# reefingBrd.net
KiCad netlist of a schematic drawn in EAGLE
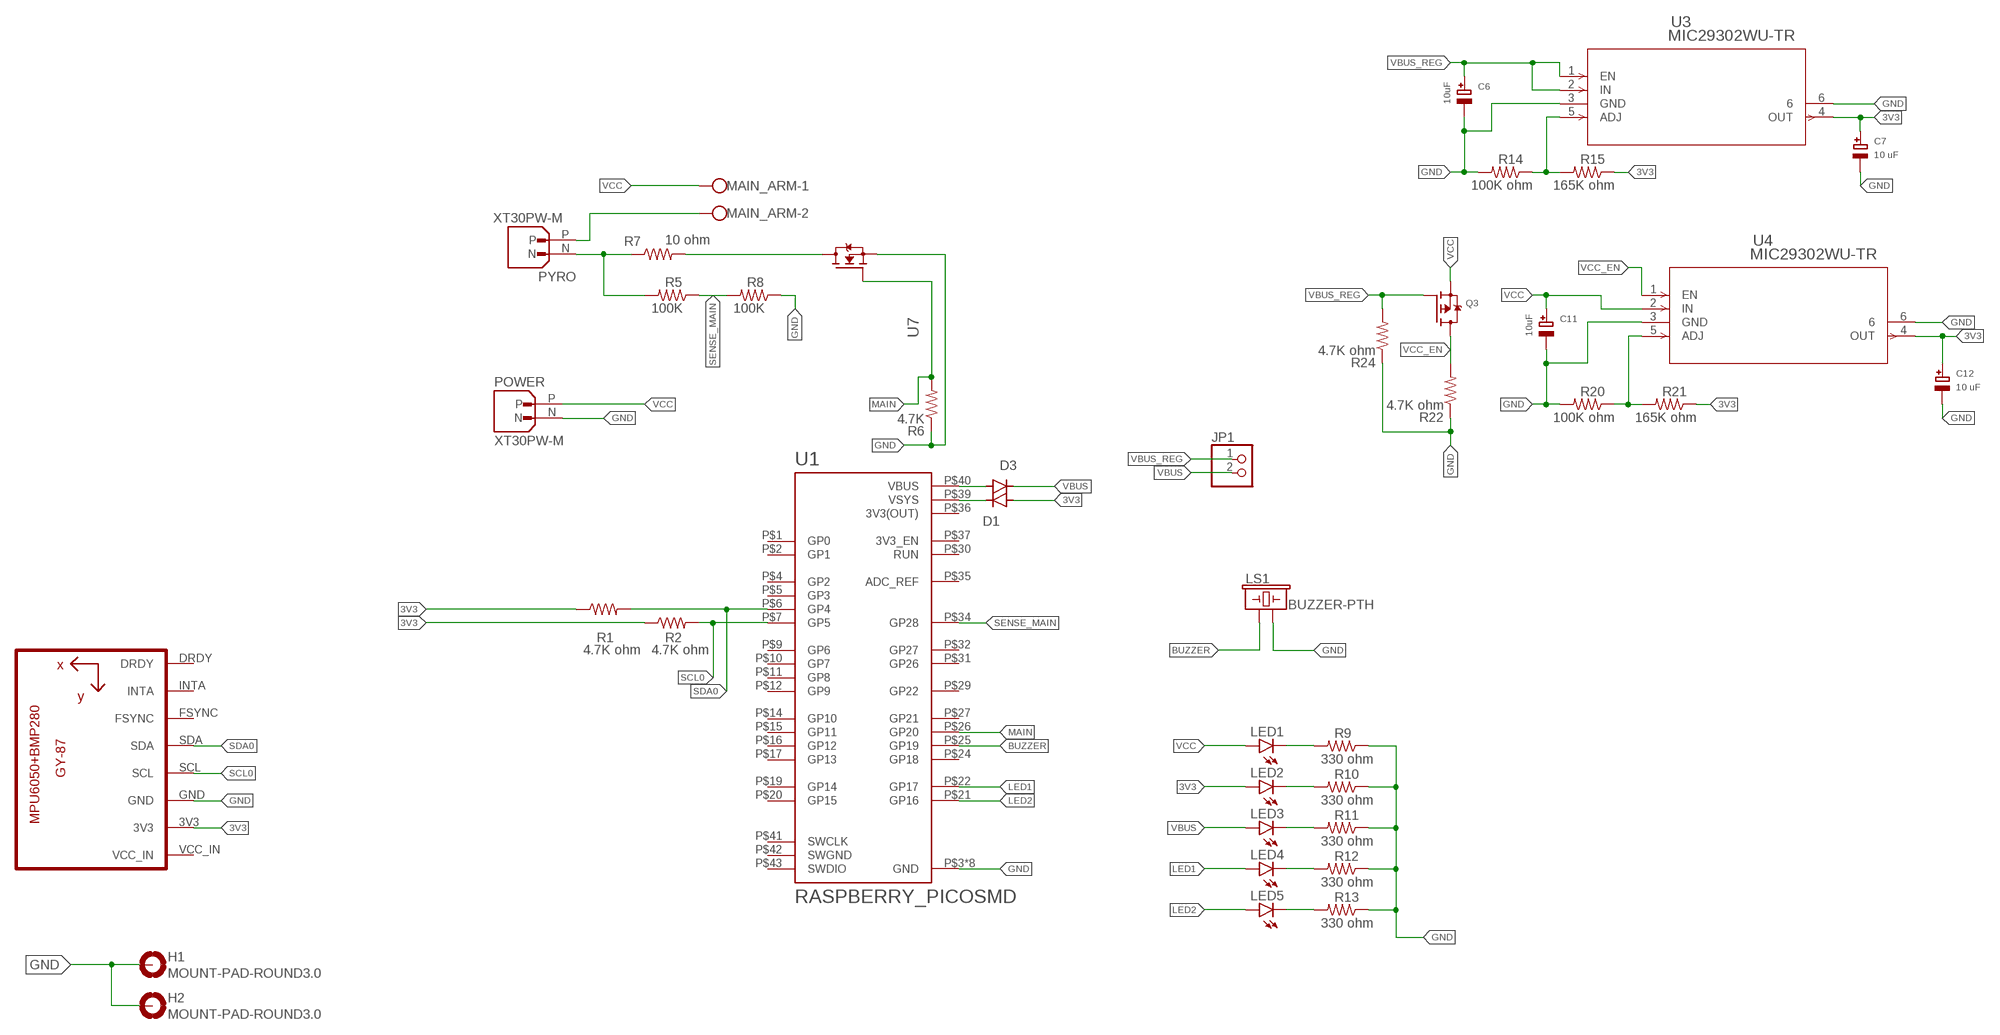
[diagram p0: schematic, sheet 1]

(export (version "E")
  (design (tool "Eeschema 10.0.6"))
  (components
    (comp (ref "C6")
      (value "10uF")
      (footprint "eagle-import:EIA3216-18_A-W")
      (libsource (lib "eagle-import") (part "CAP_TANTALUMA/3216_WAVE"))
    )
    (comp (ref "C7")
      (value "10 uF")
      (footprint "eagle-import:EIA3216-18_A-W")
      (libsource (lib "eagle-import") (part "CAP_TANTALUMA/3216_WAVE"))
    )
    (comp (ref "C11")
      (value "10uF")
      (footprint "eagle-import:EIA3216-18_A-W")
      (libsource (lib "eagle-import") (part "CAP_TANTALUMA/3216_WAVE"))
    )
    (comp (ref "C12")
      (value "10 uF")
      (footprint "eagle-import:EIA3216-18_A-W")
      (libsource (lib "eagle-import") (part "CAP_TANTALUMA/3216_WAVE"))
    )
    (comp (ref "D1")
      (value "1N4004")
      (footprint "eagle-import:DO41-10")
      (libsource (lib "eagle-import") (part "1N4004"))
    )
    (comp (ref "D3")
      (value "1N4004")
      (footprint "eagle-import:DO41-10")
      (libsource (lib "eagle-import") (part "1N4004"))
    )
    (comp (ref "H1")
      (value "MOUNT-PAD-ROUND3.0")
      (footprint "eagle-import:3,0-PAD")
      (libsource (lib "eagle-import") (part "MOUNT-PAD-ROUND3.0"))
    )
    (comp (ref "H2")
      (value "MOUNT-PAD-ROUND3.0")
      (footprint "eagle-import:3,0-PAD")
      (libsource (lib "eagle-import") (part "MOUNT-PAD-ROUND3.0"))
    )
    (comp (ref "JP1")
      (value "PINHD-1X2")
      (footprint "eagle-import:1X02")
      (libsource (lib "eagle-import") (part "PINHD-1X2"))
    )
    (comp (ref "LED1")
      (value "LEDCHIPLED_1206")
      (footprint "eagle-import:CHIPLED_1206")
      (libsource (lib "eagle-import") (part "LEDCHIPLED_1206"))
    )
    (comp (ref "LED2")
      (value "LEDCHIPLED_1206")
      (footprint "eagle-import:CHIPLED_1206")
      (libsource (lib "eagle-import") (part "LEDCHIPLED_1206"))
    )
    (comp (ref "LED3")
      (value "LEDCHIPLED_1206")
      (footprint "eagle-import:CHIPLED_1206")
      (libsource (lib "eagle-import") (part "LEDCHIPLED_1206"))
    )
    (comp (ref "LED4")
      (value "LEDCHIPLED_1206")
      (footprint "eagle-import:CHIPLED_1206")
      (libsource (lib "eagle-import") (part "LEDCHIPLED_1206"))
    )
    (comp (ref "LED5")
      (value "LEDCHIPLED_1206")
      (footprint "eagle-import:CHIPLED_1206")
      (libsource (lib "eagle-import") (part "LEDCHIPLED_1206"))
    )
    (comp (ref "LS1")
      (value "BUZZER-PTH")
      (footprint "eagle-import:BUZZER-12MM")
      (libsource (lib "eagle-import") (part "BUZZER-PTH"))
    )
    (comp (ref "MAIN_ARM")
      (value "W237-102")
      (footprint "eagle-import:W237-102")
      (fields (field (name "MPN") "237-102"))
      (libsource (lib "eagle-import") (part "W237-102"))
    )
    (comp (ref "POWER")
      (value "XT30PW-M")
      (footprint "eagle-import:AMASS_XT30PW-M")
      (fields (field (name "MF") "AMASS"))
      (libsource (lib "eagle-import") (part "XT30PW-M"))
    )
    (comp (ref "PYRO")
      (value "XT30PW-M")
      (footprint "eagle-import:AMASS_XT30PW-M")
      (fields (field (name "MF") "AMASS"))
      (libsource (lib "eagle-import") (part "XT30PW-M"))
    )
    (comp (ref "Q3")
      (value "MOSFET-PWIDE")
      (footprint "eagle-import:SOT23-WIDE")
      (libsource (lib "eagle-import") (part "MOSFET-PWIDE"))
    )
    (comp (ref "R1")
      (value "4.7K ohm")
      (footprint "eagle-import:R0805")
      (libsource (lib "eagle-import") (part "R-US_R0805"))
    )
    (comp (ref "R2")
      (value "4.7K ohm")
      (footprint "eagle-import:R0805")
      (libsource (lib "eagle-import") (part "R-US_R0805"))
    )
    (comp (ref "R5")
      (value "100K")
      (footprint "eagle-import:R0805")
      (libsource (lib "eagle-import") (part "R-US_R0805"))
    )
    (comp (ref "R6")
      (value "4.7K")
      (footprint "eagle-import:R0805")
      (libsource (lib "eagle-import") (part "R-US_R0805"))
    )
    (comp (ref "R7")
      (value "10 ohm")
      (footprint "eagle-import:0207_10")
      (libsource (lib "eagle-import") (part "R-US_0207/10"))
    )
    (comp (ref "R8")
      (value "100K")
      (footprint "eagle-import:R0805")
      (libsource (lib "eagle-import") (part "R-US_R0805"))
    )
    (comp (ref "R9")
      (value "330 ohm")
      (footprint "eagle-import:R0805")
      (libsource (lib "eagle-import") (part "R-US_R0805"))
    )
    (comp (ref "R10")
      (value "330 ohm")
      (footprint "eagle-import:R0805")
      (libsource (lib "eagle-import") (part "R-US_R0805"))
    )
    (comp (ref "R11")
      (value "330 ohm")
      (footprint "eagle-import:R0805")
      (libsource (lib "eagle-import") (part "R-US_R0805"))
    )
    (comp (ref "R12")
      (value "330 ohm")
      (footprint "eagle-import:R0805")
      (libsource (lib "eagle-import") (part "R-US_R0805"))
    )
    (comp (ref "R13")
      (value "330 ohm")
      (footprint "eagle-import:R0805")
      (libsource (lib "eagle-import") (part "R-US_R0805"))
    )
    (comp (ref "R14")
      (value "100K ohm")
      (footprint "eagle-import:R0805")
      (libsource (lib "eagle-import") (part "R-US_R0805"))
    )
    (comp (ref "R15")
      (value "165K ohm")
      (footprint "eagle-import:R0805")
      (libsource (lib "eagle-import") (part "R-US_R0805"))
    )
    (comp (ref "R20")
      (value "100K ohm")
      (footprint "eagle-import:R0805")
      (libsource (lib "eagle-import") (part "R-US_R0805"))
    )
    (comp (ref "R21")
      (value "165K ohm")
      (footprint "eagle-import:R0805")
      (libsource (lib "eagle-import") (part "R-US_R0805"))
    )
    (comp (ref "R22")
      (value "4.7K ohm")
      (footprint "eagle-import:R0805")
      (libsource (lib "eagle-import") (part "R-US_R0805"))
    )
    (comp (ref "R24")
      (value "4.7K ohm")
      (footprint "eagle-import:R0805")
      (libsource (lib "eagle-import") (part "R-US_R0805"))
    )
    (comp (ref "U1")
      (value "RASPBERRY_PICOSMD")
      (footprint "eagle-import:PICO-PKG-SMD")
      (libsource (lib "eagle-import") (part "RASPBERRY_PICOSMD"))
    )
    (comp (ref "U2")
      (value "GY-521MPU6050")
      (footprint "eagle-import:GY-521")
      (libsource (lib "eagle-import") (part "GY-521MPU6050"))
    )
    (comp (ref "U3")
      (value "MIC29302WU-TR")
      (footprint "eagle-import:TO-263-5_MCH")
      (fields (field (name "COPYRIGHT") "Copyright (C) 2024 Ultra Librarian. All rights reserved."))
      (libsource (lib "eagle-import") (part "MIC29302WU-TR"))
    )
    (comp (ref "U4")
      (value "MIC29302WU-TR")
      (footprint "eagle-import:TO-263-5_MCH")
      (fields (field (name "COPYRIGHT") "Copyright (C) 2024 Ultra Librarian. All rights reserved."))
      (libsource (lib "eagle-import") (part "MIC29302WU-TR"))
    )
    (comp (ref "U7")
      (value "IRF540NPBF")
      (footprint "eagle-import:TO254P1054X469X1930-3")
      (fields (field (name "MF") "Infineon"))
      (libsource (lib "eagle-import") (part "IRF540NPBF"))
    )
  )
  (nets
    (net (code "1") (name "/3V3(OUT)") (class "Default")
      (node (ref "U1") (pin "P$36") (pinfunction "3V3(OUT)_P$36") (pintype "power_in"))
    )
    (net (code "2") (name "/SWGND") (class "Default")
      (node (ref "U1") (pin "P$42") (pinfunction "SWGND_P$42") (pintype "power_in"))
    )
    (net (code "3") (name "3V3") (class "Default")
      (node (ref "C12") (pin "+") (pinfunction "+_+") (pintype "passive"))
      (node (ref "C7") (pin "+") (pinfunction "+_+") (pintype "passive"))
      (node (ref "D1") (pin "A") (pinfunction "A_A") (pintype "passive"))
      (node (ref "LED2") (pin "A") (pinfunction "A_A") (pintype "passive"))
      (node (ref "R1") (pin "1") (pinfunction "1_1") (pintype "passive"))
      (node (ref "R15") (pin "1") (pinfunction "1_1") (pintype "passive"))
      (node (ref "R2") (pin "1") (pinfunction "1_1") (pintype "passive"))
      (node (ref "R21") (pin "1") (pinfunction "1_1") (pintype "passive"))
      (node (ref "U2") (pin "3V3") (pinfunction "3V3_3V3") (pintype "bidirectional"))
      (node (ref "U3") (pin "4") (pinfunction "OUT_4") (pintype "output"))
      (node (ref "U4") (pin "4") (pinfunction "OUT_4") (pintype "output"))
    )
    (net (code "4") (name "BUZZER") (class "Default")
      (node (ref "LS1") (pin "+") (pinfunction "1_+") (pintype "passive"))
      (node (ref "U1") (pin "P$25") (pinfunction "GP19_P$25") (pintype "bidirectional"))
    )
    (net (code "5") (name "GND") (class "Default")
      (node (ref "C11") (pin "-") (pinfunction "-_-") (pintype "passive"))
      (node (ref "C12") (pin "-") (pinfunction "-_-") (pintype "passive"))
      (node (ref "C6") (pin "-") (pinfunction "-_-") (pintype "passive"))
      (node (ref "C7") (pin "-") (pinfunction "-_-") (pintype "passive"))
      (node (ref "H1") (pin "B3,0") (pinfunction "MOUNT_B3,0") (pintype "passive"))
      (node (ref "H2") (pin "B3,0") (pinfunction "MOUNT_B3,0") (pintype "passive"))
      (node (ref "LS1") (pin "-") (pinfunction "2_-") (pintype "passive"))
      (node (ref "POWER") (pin "N") (pinfunction "N_N") (pintype "power_in"))
      (node (ref "R10") (pin "1") (pinfunction "1_1") (pintype "passive"))
      (node (ref "R11") (pin "1") (pinfunction "1_1") (pintype "passive"))
      (node (ref "R12") (pin "1") (pinfunction "1_1") (pintype "passive"))
      (node (ref "R13") (pin "1") (pinfunction "1_1") (pintype "passive"))
      (node (ref "R14") (pin "2") (pinfunction "2_2") (pintype "passive"))
      (node (ref "R20") (pin "2") (pinfunction "2_2") (pintype "passive"))
      (node (ref "R22") (pin "1") (pinfunction "1_1") (pintype "passive"))
      (node (ref "R24") (pin "1") (pinfunction "1_1") (pintype "passive"))
      (node (ref "R6") (pin "1") (pinfunction "1_1") (pintype "passive"))
      (node (ref "R8") (pin "1") (pinfunction "1_1") (pintype "passive"))
      (node (ref "R9") (pin "1") (pinfunction "1_1") (pintype "passive"))
      (node (ref "U1") (pin "P$13") (pinfunction "GND_P$13") (pintype "power_in"))
      (node (ref "U1") (pin "P$18") (pinfunction "GND_P$18") (pintype "power_in"))
      (node (ref "U1") (pin "P$23") (pinfunction "GND_P$23") (pintype "power_in"))
      (node (ref "U1") (pin "P$28") (pinfunction "GND_P$28") (pintype "power_in"))
      (node (ref "U1") (pin "P$3") (pinfunction "GND_P$3") (pintype "power_in"))
      (node (ref "U1") (pin "P$33") (pinfunction "GND_P$33") (pintype "power_in"))
      (node (ref "U1") (pin "P$38") (pinfunction "GND_P$38") (pintype "power_in"))
      (node (ref "U1") (pin "P$8") (pinfunction "GND_P$8") (pintype "power_in"))
      (node (ref "U2") (pin "GND") (pinfunction "GND_GND") (pintype "bidirectional"))
      (node (ref "U3") (pin "3") (pinfunction "GND_3") (pintype "power_in"))
      (node (ref "U3") (pin "6") (pinfunction "6_6") (pintype "passive"))
      (node (ref "U4") (pin "3") (pinfunction "GND_3") (pintype "power_in"))
      (node (ref "U4") (pin "6") (pinfunction "6_6") (pintype "passive"))
      (node (ref "U7") (pin "3") (pinfunction "S_3") (pintype "passive"))
    )
    (net (code "6") (name "LED1") (class "Default")
      (node (ref "LED4") (pin "A") (pinfunction "A_A") (pintype "passive"))
      (node (ref "U1") (pin "P$22") (pinfunction "GP17_P$22") (pintype "bidirectional"))
    )
    (net (code "7") (name "LED2") (class "Default")
      (node (ref "LED5") (pin "A") (pinfunction "A_A") (pintype "passive"))
      (node (ref "U1") (pin "P$21") (pinfunction "GP16_P$21") (pintype "bidirectional"))
    )
    (net (code "8") (name "MAIN") (class "Default")
      (node (ref "R6") (pin "2") (pinfunction "2_2") (pintype "passive"))
      (node (ref "U1") (pin "P$26") (pinfunction "GP20_P$26") (pintype "bidirectional"))
      (node (ref "U7") (pin "1") (pinfunction "G_1") (pintype "passive"))
    )
    (net (code "9") (name "Net-(LED1-PadC)") (class "Default")
      (node (ref "LED1") (pin "C") (pinfunction "C_C") (pintype "passive"))
      (node (ref "R9") (pin "2") (pinfunction "2_2") (pintype "passive"))
    )
    (net (code "10") (name "Net-(LED2-PadC)") (class "Default")
      (node (ref "LED2") (pin "C") (pinfunction "C_C") (pintype "passive"))
      (node (ref "R10") (pin "2") (pinfunction "2_2") (pintype "passive"))
    )
    (net (code "11") (name "Net-(LED3-PadC)") (class "Default")
      (node (ref "LED3") (pin "C") (pinfunction "C_C") (pintype "passive"))
      (node (ref "R11") (pin "2") (pinfunction "2_2") (pintype "passive"))
    )
    (net (code "12") (name "Net-(LED4-PadC)") (class "Default")
      (node (ref "LED4") (pin "C") (pinfunction "C_C") (pintype "passive"))
      (node (ref "R12") (pin "2") (pinfunction "2_2") (pintype "passive"))
    )
    (net (code "13") (name "Net-(LED5-PadC)") (class "Default")
      (node (ref "LED5") (pin "C") (pinfunction "C_C") (pintype "passive"))
      (node (ref "R13") (pin "2") (pinfunction "2_2") (pintype "passive"))
    )
    (net (code "14") (name "Net-(MAIN_ARMB-KL)") (class "Default")
      (node (ref "MAIN_ARM") (pin "2") (pinfunction "KL_2") (pintype "passive"))
      (node (ref "PYRO") (pin "P") (pinfunction "P_P") (pintype "power_in"))
    )
    (net (code "15") (name "Net-(PYRO-PadN)") (class "Default")
      (node (ref "PYRO") (pin "N") (pinfunction "N_N") (pintype "power_in"))
      (node (ref "R5") (pin "2") (pinfunction "2_2") (pintype "passive"))
      (node (ref "R7") (pin "1") (pinfunction "1_1") (pintype "passive"))
    )
    (net (code "16") (name "Net-(U1-VBUS)") (class "Default")
      (node (ref "D3") (pin "A") (pinfunction "A_A") (pintype "passive"))
      (node (ref "U1") (pin "P$40") (pinfunction "VBUS_P$40") (pintype "power_in"))
    )
    (net (code "17") (name "Net-(U1-VSYS)") (class "Default")
      (node (ref "D1") (pin "C") (pinfunction "C_C") (pintype "passive"))
      (node (ref "U1") (pin "P$39") (pinfunction "VSYS_P$39") (pintype "power_in"))
    )
    (net (code "18") (name "Net-(U3-ADJ)") (class "Default")
      (node (ref "R14") (pin "1") (pinfunction "1_1") (pintype "passive"))
      (node (ref "R15") (pin "2") (pinfunction "2_2") (pintype "passive"))
      (node (ref "U3") (pin "5") (pinfunction "ADJ_5") (pintype "input"))
    )
    (net (code "19") (name "Net-(U4-ADJ)") (class "Default")
      (node (ref "R20") (pin "1") (pinfunction "1_1") (pintype "passive"))
      (node (ref "R21") (pin "2") (pinfunction "2_2") (pintype "passive"))
      (node (ref "U4") (pin "5") (pinfunction "ADJ_5") (pintype "input"))
    )
    (net (code "20") (name "Net-(U7-D)") (class "Default")
      (node (ref "R7") (pin "2") (pinfunction "2_2") (pintype "passive"))
      (node (ref "U7") (pin "2") (pinfunction "D_2") (pintype "passive"))
    )
    (net (code "21") (name "SCL0") (class "Default")
      (node (ref "R2") (pin "2") (pinfunction "2_2") (pintype "passive"))
      (node (ref "U1") (pin "P$7") (pinfunction "GP5_P$7") (pintype "bidirectional"))
      (node (ref "U2") (pin "SCL") (pinfunction "SCL_SCL") (pintype "bidirectional"))
    )
    (net (code "22") (name "SDA0") (class "Default")
      (node (ref "R1") (pin "2") (pinfunction "2_2") (pintype "passive"))
      (node (ref "U1") (pin "P$6") (pinfunction "GP4_P$6") (pintype "bidirectional"))
      (node (ref "U2") (pin "SDA") (pinfunction "SDA_SDA") (pintype "bidirectional"))
    )
    (net (code "23") (name "SENSE_MAIN") (class "Default")
      (node (ref "R5") (pin "1") (pinfunction "1_1") (pintype "passive"))
      (node (ref "R8") (pin "2") (pinfunction "2_2") (pintype "passive"))
      (node (ref "U1") (pin "P$34") (pinfunction "GP28_P$34") (pintype "bidirectional"))
    )
    (net (code "24") (name "VBUS") (class "Default")
      (node (ref "D3") (pin "C") (pinfunction "C_C") (pintype "passive"))
      (node (ref "JP1") (pin "2") (pinfunction "2_2") (pintype "passive"))
      (node (ref "LED3") (pin "A") (pinfunction "A_A") (pintype "passive"))
    )
    (net (code "25") (name "VBUS_REG") (class "Default")
      (node (ref "C6") (pin "+") (pinfunction "+_+") (pintype "passive"))
      (node (ref "JP1") (pin "1") (pinfunction "1_1") (pintype "passive"))
      (node (ref "Q3") (pin "1") (pinfunction "G_1") (pintype "passive"))
      (node (ref "R24") (pin "2") (pinfunction "2_2") (pintype "passive"))
      (node (ref "U3") (pin "1") (pinfunction "EN_1") (pintype "input"))
      (node (ref "U3") (pin "2") (pinfunction "IN_2") (pintype "input"))
    )
    (net (code "26") (name "VCC") (class "Default")
      (node (ref "C11") (pin "+") (pinfunction "+_+") (pintype "passive"))
      (node (ref "LED1") (pin "A") (pinfunction "A_A") (pintype "passive"))
      (node (ref "MAIN_ARM") (pin "1") (pinfunction "KL_1") (pintype "passive"))
      (node (ref "POWER") (pin "P") (pinfunction "P_P") (pintype "power_in"))
      (node (ref "Q3") (pin "2") (pinfunction "S_2") (pintype "passive"))
      (node (ref "U4") (pin "2") (pinfunction "IN_2") (pintype "input"))
    )
    (net (code "27") (name "VCC_EN") (class "Default")
      (node (ref "Q3") (pin "3") (pinfunction "D_3") (pintype "passive"))
      (node (ref "R22") (pin "2") (pinfunction "2_2") (pintype "passive"))
      (node (ref "U4") (pin "1") (pinfunction "EN_1") (pintype "input"))
    )
    (net (code "28") (name "unconnected-(U1-3V3_EN-PadP$37)") (class "Default")
      (node (ref "U1") (pin "P$37") (pinfunction "3V3_EN_P$37") (pintype "input"))
    )
    (net (code "29") (name "unconnected-(U1-ADC_REF-PadP$35)") (class "Default")
      (node (ref "U1") (pin "P$35") (pinfunction "ADC_REF_P$35") (pintype "input"))
    )
    (net (code "30") (name "unconnected-(U1-GP0-PadP$1)") (class "Default")
      (node (ref "U1") (pin "P$1") (pinfunction "GP0_P$1") (pintype "bidirectional"))
    )
    (net (code "31") (name "unconnected-(U1-GP1-PadP$2)") (class "Default")
      (node (ref "U1") (pin "P$2") (pinfunction "GP1_P$2") (pintype "bidirectional"))
    )
    (net (code "32") (name "unconnected-(U1-GP2-PadP$4)") (class "Default")
      (node (ref "U1") (pin "P$4") (pinfunction "GP2_P$4") (pintype "bidirectional"))
    )
    (net (code "33") (name "unconnected-(U1-GP3-PadP$5)") (class "Default")
      (node (ref "U1") (pin "P$5") (pinfunction "GP3_P$5") (pintype "bidirectional"))
    )
    (net (code "34") (name "unconnected-(U1-GP6-PadP$9)") (class "Default")
      (node (ref "U1") (pin "P$9") (pinfunction "GP6_P$9") (pintype "bidirectional"))
    )
    (net (code "35") (name "unconnected-(U1-GP7-PadP$10)") (class "Default")
      (node (ref "U1") (pin "P$10") (pinfunction "GP7_P$10") (pintype "bidirectional"))
    )
    (net (code "36") (name "unconnected-(U1-GP8-PadP$11)") (class "Default")
      (node (ref "U1") (pin "P$11") (pinfunction "GP8_P$11") (pintype "bidirectional"))
    )
    (net (code "37") (name "unconnected-(U1-GP9-PadP$12)") (class "Default")
      (node (ref "U1") (pin "P$12") (pinfunction "GP9_P$12") (pintype "bidirectional"))
    )
    (net (code "38") (name "unconnected-(U1-GP10-PadP$14)") (class "Default")
      (node (ref "U1") (pin "P$14") (pinfunction "GP10_P$14") (pintype "bidirectional"))
    )
    (net (code "39") (name "unconnected-(U1-GP11-PadP$15)") (class "Default")
      (node (ref "U1") (pin "P$15") (pinfunction "GP11_P$15") (pintype "bidirectional"))
    )
    (net (code "40") (name "unconnected-(U1-GP12-PadP$16)") (class "Default")
      (node (ref "U1") (pin "P$16") (pinfunction "GP12_P$16") (pintype "bidirectional"))
    )
    (net (code "41") (name "unconnected-(U1-GP13-PadP$17)") (class "Default")
      (node (ref "U1") (pin "P$17") (pinfunction "GP13_P$17") (pintype "bidirectional"))
    )
    (net (code "42") (name "unconnected-(U1-GP14-PadP$19)") (class "Default")
      (node (ref "U1") (pin "P$19") (pinfunction "GP14_P$19") (pintype "bidirectional"))
    )
    (net (code "43") (name "unconnected-(U1-GP15-PadP$20)") (class "Default")
      (node (ref "U1") (pin "P$20") (pinfunction "GP15_P$20") (pintype "bidirectional"))
    )
    (net (code "44") (name "unconnected-(U1-GP18-PadP$24)") (class "Default")
      (node (ref "U1") (pin "P$24") (pinfunction "GP18_P$24") (pintype "bidirectional"))
    )
    (net (code "45") (name "unconnected-(U1-GP21-PadP$27)") (class "Default")
      (node (ref "U1") (pin "P$27") (pinfunction "GP21_P$27") (pintype "bidirectional"))
    )
    (net (code "46") (name "unconnected-(U1-GP22-PadP$29)") (class "Default")
      (node (ref "U1") (pin "P$29") (pinfunction "GP22_P$29") (pintype "bidirectional"))
    )
    (net (code "47") (name "unconnected-(U1-GP26-PadP$31)") (class "Default")
      (node (ref "U1") (pin "P$31") (pinfunction "GP26_P$31") (pintype "bidirectional"))
    )
    (net (code "48") (name "unconnected-(U1-GP27-PadP$32)") (class "Default")
      (node (ref "U1") (pin "P$32") (pinfunction "GP27_P$32") (pintype "bidirectional"))
    )
    (net (code "49") (name "unconnected-(U1-RUN-PadP$30)") (class "Default")
      (node (ref "U1") (pin "P$30") (pinfunction "RUN_P$30") (pintype "input"))
    )
    (net (code "50") (name "unconnected-(U1-SWCLK-PadP$41)") (class "Default")
      (node (ref "U1") (pin "P$41") (pinfunction "SWCLK_P$41") (pintype "input"))
    )
    (net (code "51") (name "unconnected-(U1-SWDIO-PadP$43)") (class "Default")
      (node (ref "U1") (pin "P$43") (pinfunction "SWDIO_P$43") (pintype "bidirectional"))
    )
    (net (code "52") (name "unconnected-(U2-PadDRDY)") (class "Default")
      (node (ref "U2") (pin "DRDY") (pinfunction "DRDY_DRDY") (pintype "bidirectional"))
    )
    (net (code "53") (name "unconnected-(U2-PadFSYNC)") (class "Default")
      (node (ref "U2") (pin "FSYNC") (pinfunction "FSYNC_FSYNC") (pintype "bidirectional"))
    )
    (net (code "54") (name "unconnected-(U2-PadINTA)") (class "Default")
      (node (ref "U2") (pin "INTA") (pinfunction "INTA_INTA") (pintype "bidirectional"))
    )
    (net (code "55") (name "unconnected-(U2-PadVCC_IN)") (class "Default")
      (node (ref "U2") (pin "VCC_IN") (pinfunction "VCC_IN_VCC_IN") (pintype "bidirectional"))
    )
  )
)
